# 12v5vVoltageRegulator.net
KiCad netlist of a schematic drawn in Altium Designer
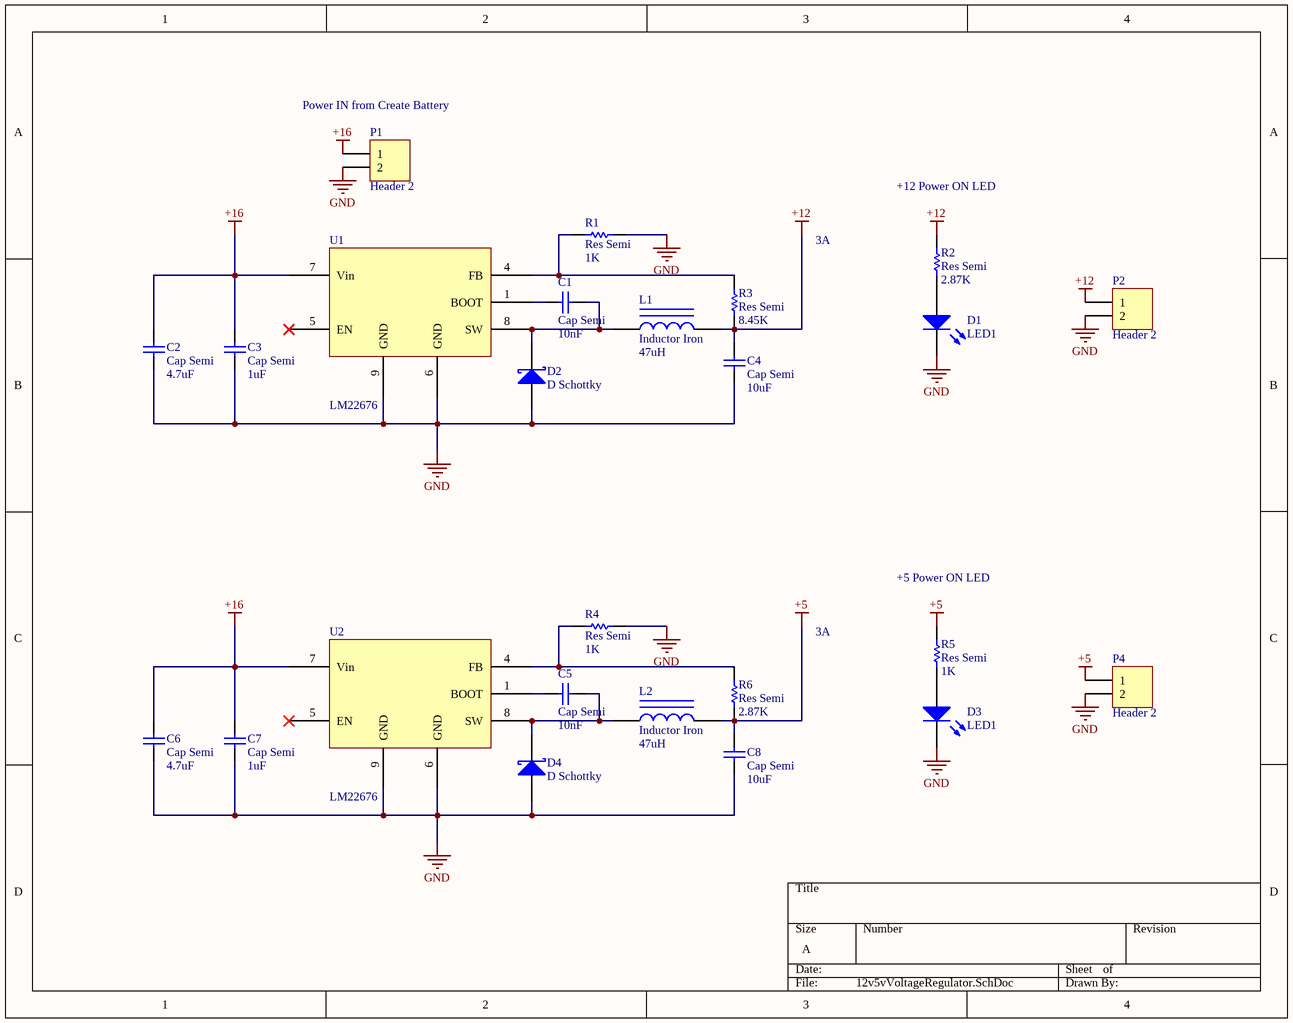
[diagram p0: 12v5vVoltageRegulator.SchDoc]

(export (version "E")
  (design (tool "Eeschema 10.0.6"))
  (components
    (comp (ref "C1")
      (value "Cap Semi")
      (footprint "CAPC2012L")
      (description "Capacitor (Semiconductor SIM Model)")
      (fields (field (name "ALTIUM_VALUE") "10nF") (field (name "PUBLISHER") "Altium Limited"))
      (libsource (lib "GpioPowerAddonLib") (part "Cap Semi"))
    )
    (comp (ref "C2")
      (value "Cap Semi")
      (footprint "CAPC4532L")
      (description "Capacitor (Semiconductor SIM Model)")
      (fields (field (name "ALTIUM_VALUE") "4.7uF") (field (name "PUBLISHER") "Altium Limited"))
      (libsource (lib "GpioPowerAddonLib") (part "Cap Semi"))
    )
    (comp (ref "C3")
      (value "Cap Semi")
      (footprint "CAPC2012L")
      (description "Capacitor (Semiconductor SIM Model)")
      (fields (field (name "ALTIUM_VALUE") "1uF") (field (name "PUBLISHER") "Altium Limited"))
      (libsource (lib "GpioPowerAddonLib") (part "Cap Semi"))
    )
    (comp (ref "C4")
      (value "Cap Semi")
      (footprint "CAPC3216L")
      (description "Capacitor (Semiconductor SIM Model)")
      (fields (field (name "ALTIUM_VALUE") "10uF") (field (name "PUBLISHER") "Altium Limited"))
      (libsource (lib "GpioPowerAddonLib") (part "Cap Semi"))
    )
    (comp (ref "C5")
      (value "Cap Semi")
      (footprint "CAPC2012L")
      (description "Capacitor (Semiconductor SIM Model)")
      (fields (field (name "ALTIUM_VALUE") "10nF") (field (name "PUBLISHER") "Altium Limited"))
      (libsource (lib "GpioPowerAddonLib") (part "Cap Semi"))
    )
    (comp (ref "C6")
      (value "Cap Semi")
      (footprint "CAPC4532L")
      (description "Capacitor (Semiconductor SIM Model)")
      (fields (field (name "ALTIUM_VALUE") "4.7uF") (field (name "PUBLISHER") "Altium Limited"))
      (libsource (lib "GpioPowerAddonLib") (part "Cap Semi"))
    )
    (comp (ref "C7")
      (value "Cap Semi")
      (footprint "CAPC2012L")
      (description "Capacitor (Semiconductor SIM Model)")
      (fields (field (name "ALTIUM_VALUE") "1uF") (field (name "PUBLISHER") "Altium Limited"))
      (libsource (lib "GpioPowerAddonLib") (part "Cap Semi"))
    )
    (comp (ref "C8")
      (value "Cap Semi")
      (footprint "CAPC3216L")
      (description "Capacitor (Semiconductor SIM Model)")
      (fields (field (name "ALTIUM_VALUE") "10uF") (field (name "PUBLISHER") "Altium Limited"))
      (libsource (lib "GpioPowerAddonLib") (part "Cap Semi"))
    )
    (comp (ref "D1")
      (value "LED1")
      (footprint "1206 - LED")
      (description "Typical RED GaAs LED")
      (fields (field (name "PUBLISHER") "Altium Limited"))
      (libsource (lib "GpioPowerAddonLib") (part "LED1"))
    )
    (comp (ref "D2")
      (value "D Schottky")
      (footprint "SMA")
      (description "Schottky Diode")
      (fields (field (name "PUBLISHER") "Altium Limited"))
      (libsource (lib "GpioPowerAddonLib") (part "D Schottky"))
    )
    (comp (ref "D3")
      (value "LED1")
      (footprint "1206 - LED")
      (description "Typical RED GaAs LED")
      (fields (field (name "PUBLISHER") "Altium Limited"))
      (libsource (lib "GpioPowerAddonLib") (part "LED1"))
    )
    (comp (ref "D4")
      (value "D Schottky")
      (footprint "SMA")
      (description "Schottky Diode")
      (fields (field (name "PUBLISHER") "Altium Limited"))
      (libsource (lib "GpioPowerAddonLib") (part "D Schottky"))
    )
    (comp (ref "L1")
      (value "Inductor Iron")
      (footprint "SRR1260")
      (description "Magnetic-Core Inductor")
      (fields (field (name "ALTIUM_VALUE") "47uH") (field (name "PUBLISHER") "Altium Limited"))
      (libsource (lib "GpioPowerAddonLib") (part "Inductor Iron"))
    )
    (comp (ref "L2")
      (value "Inductor Iron")
      (footprint "SRR1260")
      (description "Magnetic-Core Inductor")
      (fields (field (name "ALTIUM_VALUE") "47uH") (field (name "PUBLISHER") "Altium Limited"))
      (libsource (lib "GpioPowerAddonLib") (part "Inductor Iron"))
    )
    (comp (ref "P1")
      (value "Header 2")
      (footprint "Connector Molex 2")
      (description "Header, 2-Pin")
      (fields (field (name "PUBLISHER") "Altium Limited"))
      (libsource (lib "GpioPowerAddonLib") (part "Header 2"))
    )
    (comp (ref "P2")
      (value "Header 2")
      (footprint "Connector Molex 2")
      (description "Header, 2-Pin")
      (fields (field (name "PUBLISHER") "Altium Limited"))
      (libsource (lib "GpioPowerAddonLib") (part "Header 2"))
    )
    (comp (ref "P4")
      (value "Header 2")
      (footprint "Connector Molex 2")
      (description "Header, 2-Pin")
      (fields (field (name "PUBLISHER") "Altium Limited"))
      (libsource (lib "GpioPowerAddonLib") (part "Header 2"))
    )
    (comp (ref "R1")
      (value "Res Semi")
      (footprint "RESC2012N")
      (description "Semiconductor Resistor")
      (fields (field (name "ALTIUM_VALUE") "1K") (field (name "PUBLISHER") "Altium Limited"))
      (libsource (lib "GpioPowerAddonLib") (part "Res Semi"))
    )
    (comp (ref "R2")
      (value "Res Semi")
      (footprint "RESC2012N")
      (description "Semiconductor Resistor")
      (fields (field (name "ALTIUM_VALUE") "2.87K") (field (name "PUBLISHER") "Altium Limited"))
      (libsource (lib "GpioPowerAddonLib") (part "Res Semi"))
    )
    (comp (ref "R3")
      (value "Res Semi")
      (footprint "RESC2012N")
      (description "Semiconductor Resistor")
      (fields (field (name "ALTIUM_VALUE") "8.45K") (field (name "PUBLISHER") "Altium Limited"))
      (libsource (lib "GpioPowerAddonLib") (part "Res Semi"))
    )
    (comp (ref "R4")
      (value "Res Semi")
      (footprint "RESC2012N")
      (description "Semiconductor Resistor")
      (fields (field (name "ALTIUM_VALUE") "1K") (field (name "PUBLISHER") "Altium Limited"))
      (libsource (lib "GpioPowerAddonLib") (part "Res Semi"))
    )
    (comp (ref "R5")
      (value "Res Semi")
      (footprint "RESC2012N")
      (description "Semiconductor Resistor")
      (fields (field (name "ALTIUM_VALUE") "1K") (field (name "PUBLISHER") "Altium Limited"))
      (libsource (lib "GpioPowerAddonLib") (part "Res Semi"))
    )
    (comp (ref "R6")
      (value "Res Semi")
      (footprint "RESC2012N")
      (description "Semiconductor Resistor")
      (fields (field (name "ALTIUM_VALUE") "2.87K") (field (name "PUBLISHER") "Altium Limited"))
      (libsource (lib "GpioPowerAddonLib") (part "Res Semi"))
    )
    (comp (ref "U1")
      (value "LM22676")
      (footprint "LM22676")
      (description "3A SIMPLE SWITCHER")
      (libsource (lib "GpioPowerAddonLib") (part "LM22676"))
    )
    (comp (ref "U2")
      (value "LM22676")
      (footprint "LM22676")
      (description "3A SIMPLE SWITCHER")
      (libsource (lib "GpioPowerAddonLib") (part "LM22676"))
    )
  )
  (nets
    (net (code "1") (name "+5") (class "Default")
      (node (ref "C8") (pin "2") (pinfunction "2_2") (pintype "passive"))
      (node (ref "L2") (pin "2") (pinfunction "2_2") (pintype "passive"))
      (node (ref "P4") (pin "1") (pinfunction "1_1") (pintype "passive"))
      (node (ref "R5") (pin "2") (pinfunction "2_2") (pintype "passive"))
      (node (ref "R6") (pin "1") (pinfunction "1_1") (pintype "passive"))
    )
    (net (code "2") (name "+12") (class "Default")
      (node (ref "C4") (pin "2") (pinfunction "2_2") (pintype "passive"))
      (node (ref "L1") (pin "2") (pinfunction "2_2") (pintype "passive"))
      (node (ref "P2") (pin "1") (pinfunction "1_1") (pintype "passive"))
      (node (ref "R2") (pin "2") (pinfunction "2_2") (pintype "passive"))
      (node (ref "R3") (pin "1") (pinfunction "1_1") (pintype "passive"))
    )
    (net (code "3") (name "+16") (class "Default")
      (node (ref "C2") (pin "2") (pinfunction "2_2") (pintype "passive"))
      (node (ref "C3") (pin "2") (pinfunction "2_2") (pintype "passive"))
      (node (ref "C6") (pin "2") (pinfunction "2_2") (pintype "passive"))
      (node (ref "C7") (pin "2") (pinfunction "2_2") (pintype "passive"))
      (node (ref "P1") (pin "1") (pinfunction "1_1") (pintype "passive"))
      (node (ref "U1") (pin "7") (pinfunction "Vin_7") (pintype "passive"))
      (node (ref "U2") (pin "7") (pinfunction "Vin_7") (pintype "passive"))
    )
    (net (code "4") (name "GND") (class "Default")
      (node (ref "C2") (pin "1") (pinfunction "1_1") (pintype "passive"))
      (node (ref "C3") (pin "1") (pinfunction "1_1") (pintype "passive"))
      (node (ref "C4") (pin "1") (pinfunction "1_1") (pintype "passive"))
      (node (ref "C6") (pin "1") (pinfunction "1_1") (pintype "passive"))
      (node (ref "C7") (pin "1") (pinfunction "1_1") (pintype "passive"))
      (node (ref "C8") (pin "1") (pinfunction "1_1") (pintype "passive"))
      (node (ref "D1") (pin "K") (pinfunction "K_K") (pintype "passive"))
      (node (ref "D2") (pin "A") (pinfunction "A_A") (pintype "passive"))
      (node (ref "D3") (pin "K") (pinfunction "K_K") (pintype "passive"))
      (node (ref "D4") (pin "A") (pinfunction "A_A") (pintype "passive"))
      (node (ref "P1") (pin "2") (pinfunction "2_2") (pintype "passive"))
      (node (ref "P2") (pin "2") (pinfunction "2_2") (pintype "passive"))
      (node (ref "P4") (pin "2") (pinfunction "2_2") (pintype "passive"))
      (node (ref "R1") (pin "2") (pinfunction "2_2") (pintype "passive"))
      (node (ref "R4") (pin "2") (pinfunction "2_2") (pintype "passive"))
      (node (ref "U1") (pin "6") (pinfunction "GND_6") (pintype "passive"))
      (node (ref "U1") (pin "9") (pinfunction "GND_9") (pintype "passive"))
      (node (ref "U2") (pin "6") (pinfunction "GND_6") (pintype "passive"))
      (node (ref "U2") (pin "9") (pinfunction "GND_9") (pintype "passive"))
    )
    (net (code "5") (name "Net-(D1-PadA)") (class "Default")
      (node (ref "D1") (pin "A") (pinfunction "A_A") (pintype "passive"))
      (node (ref "R2") (pin "1") (pinfunction "1_1") (pintype "passive"))
    )
    (net (code "6") (name "Net-(D3-PadA)") (class "Default")
      (node (ref "D3") (pin "A") (pinfunction "A_A") (pintype "passive"))
      (node (ref "R5") (pin "1") (pinfunction "1_1") (pintype "passive"))
    )
    (net (code "7") (name "Net-(U1-BOOT)") (class "Default")
      (node (ref "C1") (pin "1") (pinfunction "1_1") (pintype "passive"))
      (node (ref "U1") (pin "1") (pinfunction "BOOT_1") (pintype "passive"))
    )
    (net (code "8") (name "Net-(U1-FB)") (class "Default")
      (node (ref "R1") (pin "1") (pinfunction "1_1") (pintype "passive"))
      (node (ref "R3") (pin "2") (pinfunction "2_2") (pintype "passive"))
      (node (ref "U1") (pin "4") (pinfunction "FB_4") (pintype "passive"))
    )
    (net (code "9") (name "Net-(U1-SW)") (class "Default")
      (node (ref "C1") (pin "2") (pinfunction "2_2") (pintype "passive"))
      (node (ref "D2") (pin "K") (pinfunction "K_K") (pintype "passive"))
      (node (ref "L1") (pin "1") (pinfunction "1_1") (pintype "passive"))
      (node (ref "U1") (pin "8") (pinfunction "SW_8") (pintype "passive"))
    )
    (net (code "10") (name "Net-(U2-BOOT)") (class "Default")
      (node (ref "C5") (pin "1") (pinfunction "1_1") (pintype "passive"))
      (node (ref "U2") (pin "1") (pinfunction "BOOT_1") (pintype "passive"))
    )
    (net (code "11") (name "Net-(U2-FB)") (class "Default")
      (node (ref "R4") (pin "1") (pinfunction "1_1") (pintype "passive"))
      (node (ref "R6") (pin "2") (pinfunction "2_2") (pintype "passive"))
      (node (ref "U2") (pin "4") (pinfunction "FB_4") (pintype "passive"))
    )
    (net (code "12") (name "Net-(U2-SW)") (class "Default")
      (node (ref "C5") (pin "2") (pinfunction "2_2") (pintype "passive"))
      (node (ref "D4") (pin "K") (pinfunction "K_K") (pintype "passive"))
      (node (ref "L2") (pin "1") (pinfunction "1_1") (pintype "passive"))
      (node (ref "U2") (pin "8") (pinfunction "SW_8") (pintype "passive"))
    )
    (net (code "13") (name "unconnected-(U1-EN-Pad5)") (class "Default")
      (node (ref "U1") (pin "5") (pinfunction "EN_5") (pintype "passive+no_connect"))
    )
    (net (code "14") (name "unconnected-(U2-EN-Pad5)") (class "Default")
      (node (ref "U2") (pin "5") (pinfunction "EN_5") (pintype "passive+no_connect"))
    )
  )
)
